# SCH_ESP32-WROOM_2022-01-13.net
KiCad netlist of a schematic drawn in EasyEDA
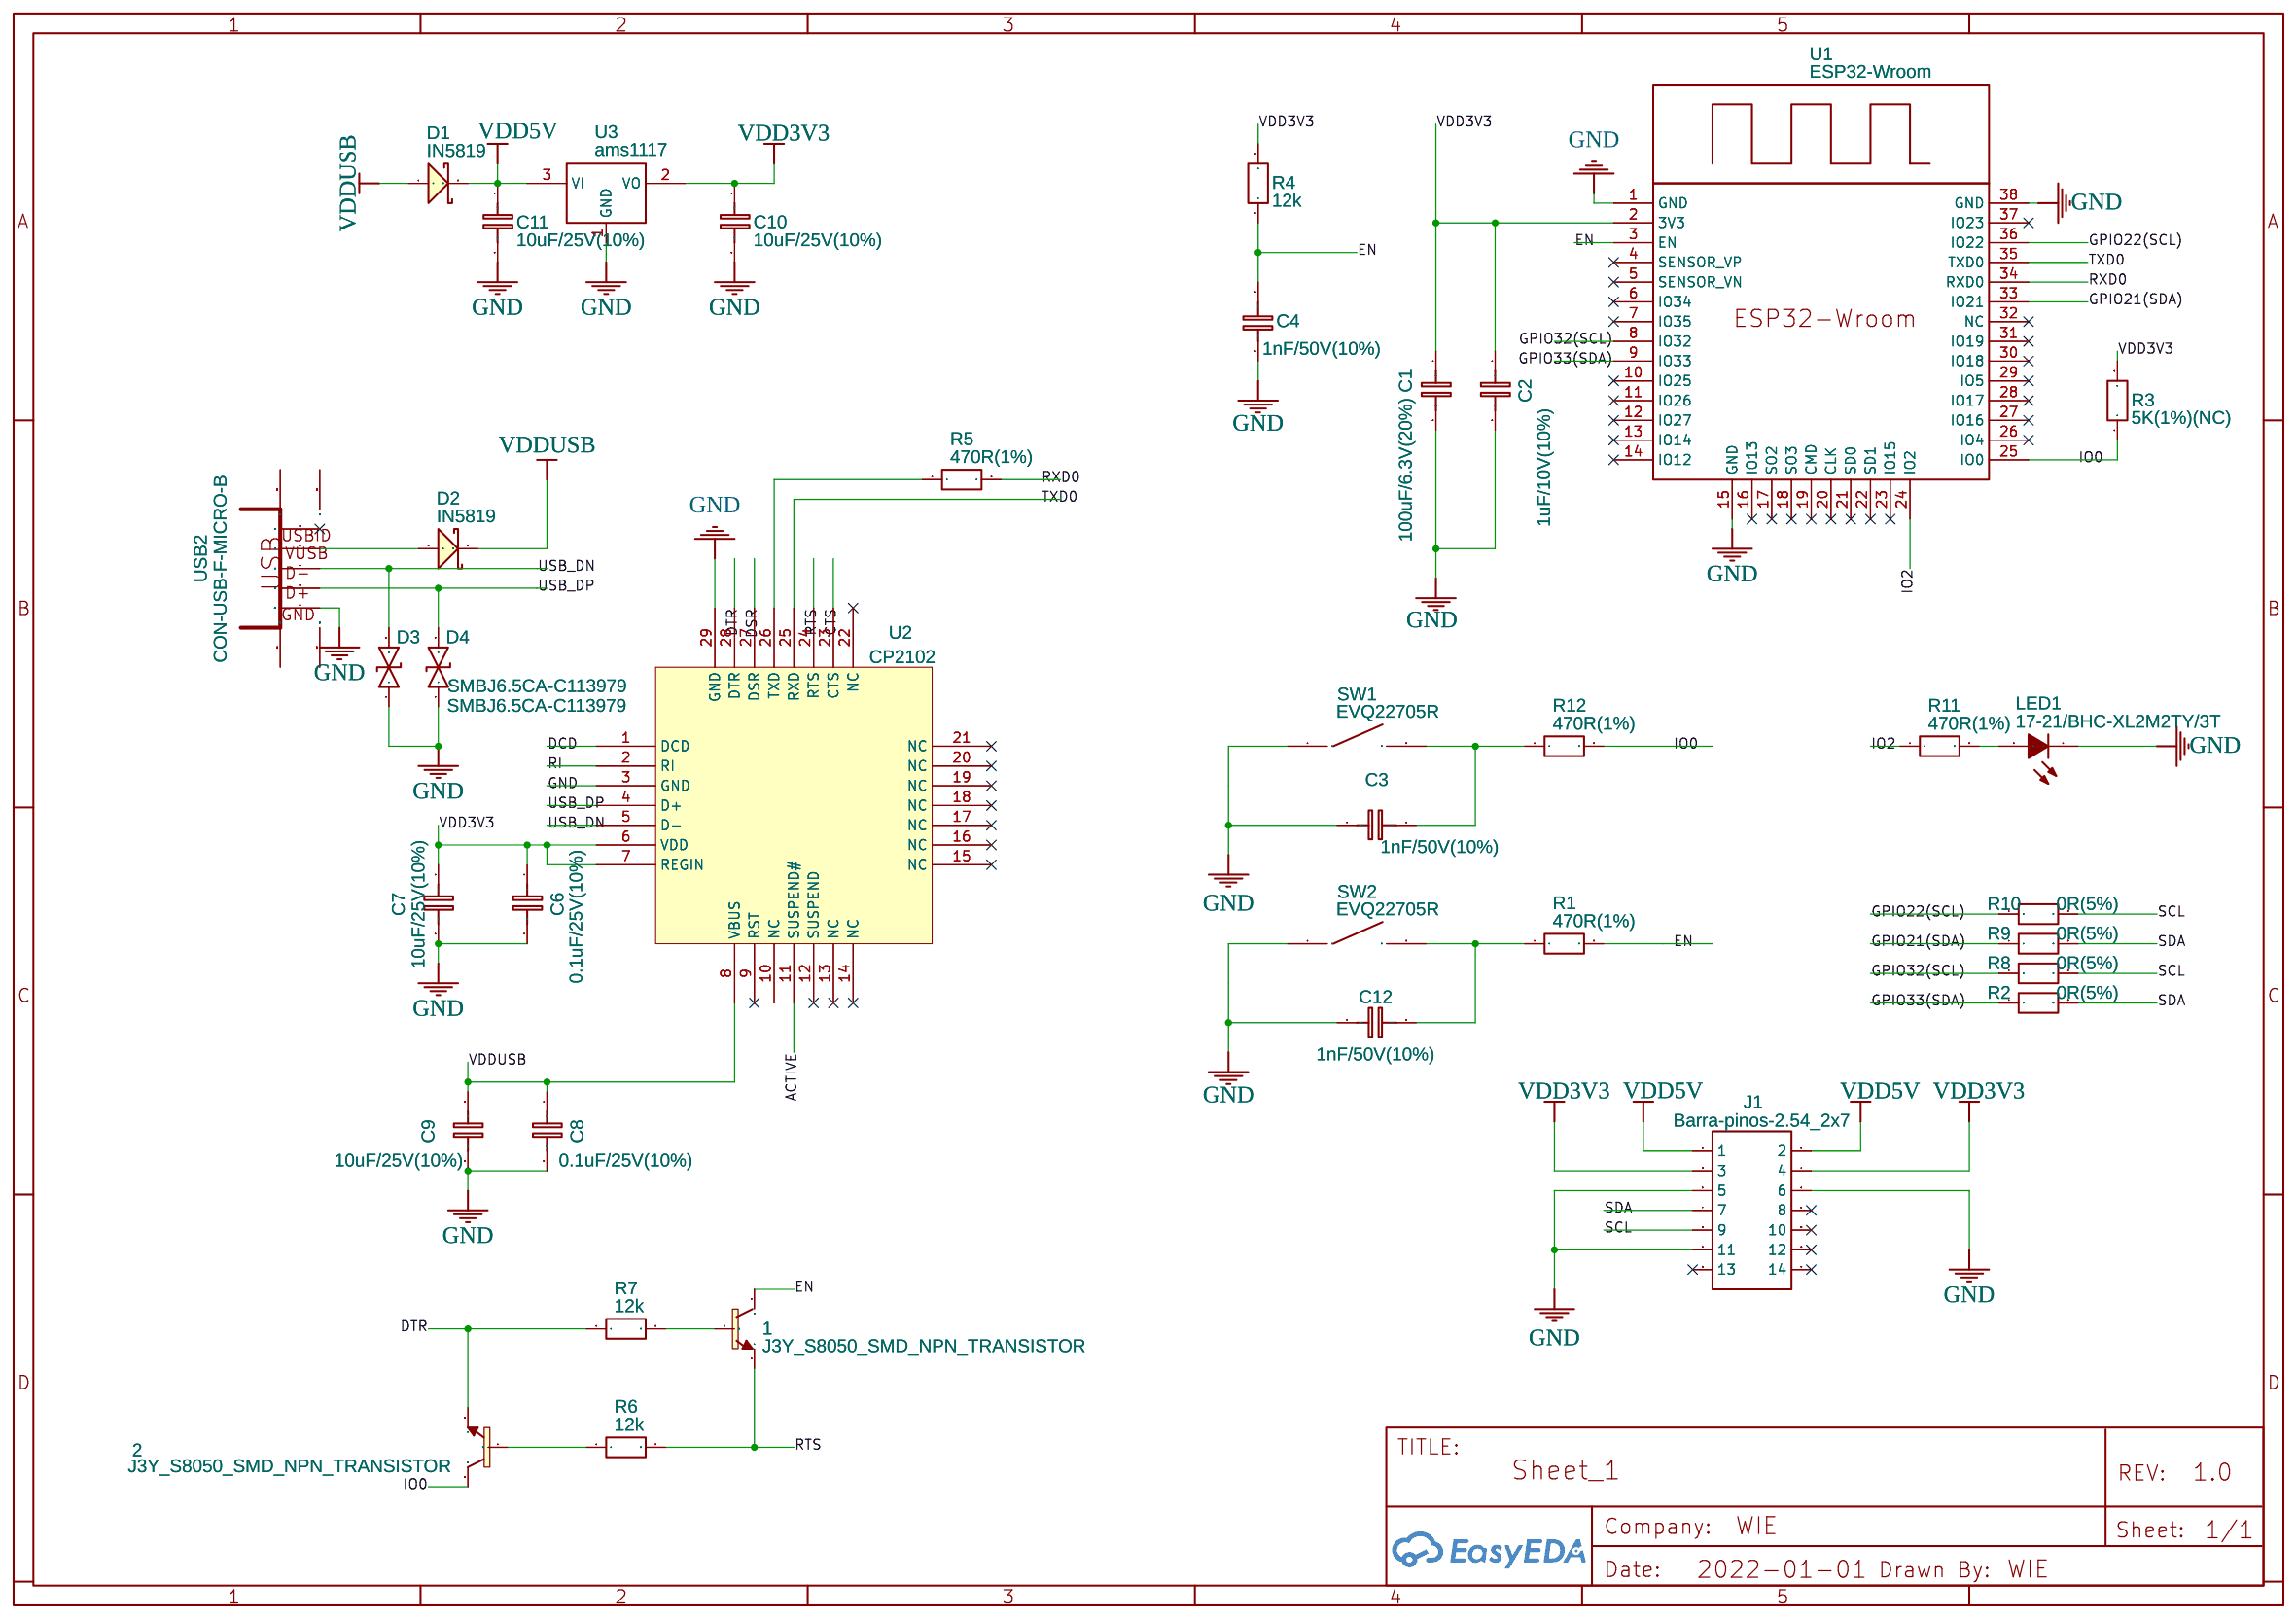
[diagram p0: schematic sheet]

(export (version "E")
  (design (tool "Eeschema 10.0.6"))
  (components
    (comp (ref "1")
      (value "J3Y_S8050_SMD_NPN_TRANSISTOR")
      (libsource (lib "") (part "J3Y_S8050_SMD_NPN_TRANSISTOR_1"))
    )
    (comp (ref "2")
      (value "J3Y_S8050_SMD_NPN_TRANSISTOR")
      (libsource (lib "") (part "J3Y_S8050_SMD_NPN_TRANSISTOR"))
    )
    (comp (ref "C1") (value "100uF/6.3V(20%)") (libsource (lib "") (part "Cap_0805_EU_1")))
    (comp (ref "C2") (value "1uF/10V(10%)") (libsource (lib "") (part "Cap_0805_EU_1")))
    (comp (ref "C3") (value "1nF/50V(10%)") (libsource (lib "") (part "Cap_0805_EU")))
    (comp (ref "C4") (value "1nF/50V(10%)") (libsource (lib "") (part "Cap_0805_EU_4")))
    (comp (ref "C6") (value "0.1uF/25V(10%)") (libsource (lib "") (part "Cap_0805_EU_2")))
    (comp (ref "C7") (value "10uF/25V(10%)") (libsource (lib "") (part "Cap_0805_EU_2")))
    (comp (ref "C8") (value "0.1uF/25V(10%)") (libsource (lib "") (part "Cap_0805_EU_2")))
    (comp (ref "C9") (value "10uF/25V(10%)") (libsource (lib "") (part "Cap_0805_EU_2")))
    (comp (ref "C10") (value "10uF/25V(10%)") (libsource (lib "") (part "Cap_0805_EU_3")))
    (comp (ref "C11") (value "10uF/25V(10%)") (libsource (lib "") (part "Cap_0805_EU_3")))
    (comp (ref "C12") (value "1nF/50V(10%)") (libsource (lib "") (part "Cap_0805_EU")))
    (comp (ref "D1") (value "IN5819") (libsource (lib "") (part "IN5819")))
    (comp (ref "D2") (value "IN5819") (libsource (lib "") (part "IN5819")))
    (comp (ref "D3")
      (value "SMBJ6.5CA-C113979")
      (fields (field (name "BOM_Manufacturer Part") "SMBJ6.5CA") (field (name "BOM_Supplier Part") "C113979"))
      (libsource (lib "") (part "SMBJ6.5CA-C113979"))
    )
    (comp (ref "D4")
      (value "SMBJ6.5CA-C113979")
      (fields (field (name "BOM_Manufacturer Part") "SMBJ6.5CA") (field (name "BOM_Supplier Part") "C113979"))
      (libsource (lib "") (part "SMBJ6.5CA-C113979"))
    )
    (comp (ref "J1")
      (value "Barra-pinos-2.54_2x7")
      (fields
        (field (name "BOM_Manufacturer Part") "Double row of needle2X7P 2.54mm")
        (field (name "BOM_Supplier Part") "C71397")
      )
      (libsource (lib "") (part "Barra-pinos-2.54_2x7"))
    )
    (comp (ref "LED1")
      (value "17-21/BHC-XL2M2TY/3T")
      (fields (field (name "BOM_Supplier Part") "C72035"))
      (libsource (lib "") (part "17-21/BHC-XL2M2TY/3T"))
    )
    (comp (ref "R1") (value "470R(1%)") (libsource (lib "") (part "Res_0805(1/8W)_EU")))
    (comp (ref "R2") (value "0R(5%)") (libsource (lib "") (part "Res_0805(1/8W)_EU")))
    (comp (ref "R3") (value "5K(1%)(NC)") (libsource (lib "") (part "Res_0805(1/8W)_EU_1")))
    (comp (ref "R4") (value "12k") (libsource (lib "") (part "Res_0805(1/8W)_EU_1")))
    (comp (ref "R5") (value "470R(1%)") (libsource (lib "") (part "Res_0805(1/8W)_EU")))
    (comp (ref "R6") (value "12k") (libsource (lib "") (part "Res_0805(1/8W)_EU")))
    (comp (ref "R7") (value "12k") (libsource (lib "") (part "Res_0805(1/8W)_EU")))
    (comp (ref "R8") (value "0R(5%)") (libsource (lib "") (part "Res_0805(1/8W)_EU")))
    (comp (ref "R9") (value "0R(5%)") (libsource (lib "") (part "Res_0805(1/8W)_EU")))
    (comp (ref "R10") (value "0R(5%)") (libsource (lib "") (part "Res_0805(1/8W)_EU")))
    (comp (ref "R11") (value "470R(1%)") (libsource (lib "") (part "Res_0805(1/8W)_EU")))
    (comp (ref "R12") (value "470R(1%)") (libsource (lib "") (part "Res_0805(1/8W)_EU")))
    (comp (ref "SW1")
      (value "EVQ22705R")
      (fields (field (name "BOM_Supplier Part") "C79156"))
      (libsource (lib "") (part "Unknown_680_-435"))
    )
    (comp (ref "SW2")
      (value "EVQ22705R")
      (fields (field (name "BOM_Supplier Part") "C79156"))
      (libsource (lib "") (part "Unknown_680_-335"))
    )
    (comp (ref "U1") (value "ESP32-Wroom") (libsource (lib "") (part "ESP32-Wroom")))
    (comp (ref "U2") (value "CP2102") (libsource (lib "") (part "CP2102")))
    (comp (ref "U3") (value "ams1117") (libsource (lib "") (part "ams1117")))
    (comp (ref "USB2") (value "CON-USB-F-MICRO-B") (libsource (lib "") (part "CON-USB-F-MICRO-B")))
  )
  (nets
    (net (code "1") (name "/ACTIVE") (class "Default")
      (node (ref "U2") (pin "11") (pinfunction "SUSPEND#_11") (pintype "unspecified"))
    )
    (net (code "2") (name "/CTS") (class "Default")
      (node (ref "U2") (pin "23") (pinfunction "CTS_23") (pintype "unspecified"))
    )
    (net (code "3") (name "/DCD") (class "Default")
      (node (ref "U2") (pin "1") (pinfunction "DCD_1") (pintype "unspecified"))
    )
    (net (code "4") (name "/DSR") (class "Default")
      (node (ref "U2") (pin "27") (pinfunction "DSR_27") (pintype "unspecified"))
    )
    (net (code "5") (name "/DTR") (class "Default")
      (node (ref "2") (pin "3") (pinfunction "E_3") (pintype "bidirectional"))
      (node (ref "R7") (pin "1") (pinfunction "1_1") (pintype "unspecified"))
      (node (ref "U2") (pin "28") (pinfunction "DTR_28") (pintype "unspecified"))
    )
    (net (code "6") (name "/EN") (class "Default")
      (node (ref "1") (pin "2") (pinfunction "C_2") (pintype "bidirectional"))
      (node (ref "C4") (pin "2") (pinfunction "2_2") (pintype "unspecified"))
      (node (ref "R1") (pin "2") (pinfunction "2_2") (pintype "unspecified"))
      (node (ref "R4") (pin "1") (pinfunction "1_1") (pintype "unspecified"))
      (node (ref "U1") (pin "3") (pinfunction "EN_3") (pintype "unspecified"))
    )
    (net (code "7") (name "/GPIO21(SDA)") (class "Default")
      (node (ref "R9") (pin "1") (pinfunction "1_1") (pintype "unspecified"))
      (node (ref "U1") (pin "33") (pinfunction "IO21_33") (pintype "unspecified"))
    )
    (net (code "8") (name "/GPIO22(SCL)") (class "Default")
      (node (ref "R10") (pin "1") (pinfunction "1_1") (pintype "unspecified"))
      (node (ref "U1") (pin "36") (pinfunction "IO22_36") (pintype "unspecified"))
    )
    (net (code "9") (name "/GPIO32(SCL)") (class "Default")
      (node (ref "R8") (pin "1") (pinfunction "1_1") (pintype "unspecified"))
      (node (ref "U1") (pin "8") (pinfunction "IO32_8") (pintype "unspecified"))
    )
    (net (code "10") (name "/GPIO33(SDA)") (class "Default")
      (node (ref "R2") (pin "1") (pinfunction "1_1") (pintype "unspecified"))
      (node (ref "U1") (pin "9") (pinfunction "IO33_9") (pintype "unspecified"))
    )
    (net (code "11") (name "/IO0") (class "Default")
      (node (ref "2") (pin "2") (pinfunction "C_2") (pintype "bidirectional"))
      (node (ref "R12") (pin "2") (pinfunction "2_2") (pintype "unspecified"))
      (node (ref "R3") (pin "1") (pinfunction "1_1") (pintype "unspecified"))
      (node (ref "U1") (pin "25") (pinfunction "IO0_25") (pintype "unspecified"))
    )
    (net (code "12") (name "/IO2") (class "Default")
      (node (ref "R11") (pin "1") (pinfunction "1_1") (pintype "unspecified"))
      (node (ref "U1") (pin "24") (pinfunction "IO2_24") (pintype "unspecified"))
    )
    (net (code "13") (name "/RI") (class "Default")
      (node (ref "U2") (pin "2") (pinfunction "RI_2") (pintype "unspecified"))
    )
    (net (code "14") (name "/RTS") (class "Default")
      (node (ref "1") (pin "3") (pinfunction "E_3") (pintype "bidirectional"))
      (node (ref "R6") (pin "2") (pinfunction "2_2") (pintype "unspecified"))
      (node (ref "U2") (pin "24") (pinfunction "RTS_24") (pintype "unspecified"))
    )
    (net (code "15") (name "/RXD0") (class "Default")
      (node (ref "R5") (pin "2") (pinfunction "2_2") (pintype "unspecified"))
      (node (ref "U1") (pin "34") (pinfunction "RXD0_34") (pintype "unspecified"))
    )
    (net (code "16") (name "/SCL") (class "Default")
      (node (ref "J1") (pin "9") (pinfunction "9_9") (pintype "input"))
      (node (ref "R10") (pin "2") (pinfunction "2_2") (pintype "unspecified"))
      (node (ref "R8") (pin "2") (pinfunction "2_2") (pintype "unspecified"))
    )
    (net (code "17") (name "/SDA") (class "Default")
      (node (ref "J1") (pin "7") (pinfunction "7_7") (pintype "input"))
      (node (ref "R2") (pin "2") (pinfunction "2_2") (pintype "unspecified"))
      (node (ref "R9") (pin "2") (pinfunction "2_2") (pintype "unspecified"))
    )
    (net (code "18") (name "/TXD0") (class "Default")
      (node (ref "U1") (pin "35") (pinfunction "TXD0_35") (pintype "unspecified"))
      (node (ref "U2") (pin "25") (pinfunction "RXD_25") (pintype "unspecified"))
    )
    (net (code "19") (name "/USB_DN") (class "Default")
      (node (ref "D3") (pin "2") (pinfunction "2_2") (pintype "unspecified"))
      (node (ref "U2") (pin "5") (pinfunction "D-_5") (pintype "unspecified"))
      (node (ref "USB2") (pin "P2") (pinfunction "D-_P2") (pintype "unspecified"))
    )
    (net (code "20") (name "/USB_DP") (class "Default")
      (node (ref "D4") (pin "2") (pinfunction "2_2") (pintype "unspecified"))
      (node (ref "U2") (pin "4") (pinfunction "D+_4") (pintype "unspecified"))
      (node (ref "USB2") (pin "P3") (pinfunction "D+_P3") (pintype "unspecified"))
    )
    (net (code "21") (name "GND") (class "Default")
      (node (ref "C1") (pin "2") (pinfunction "2_2") (pintype "unspecified"))
      (node (ref "C10") (pin "2") (pinfunction "2_2") (pintype "unspecified"))
      (node (ref "C11") (pin "2") (pinfunction "2_2") (pintype "unspecified"))
      (node (ref "C12") (pin "1") (pinfunction "1_1") (pintype "unspecified"))
      (node (ref "C2") (pin "2") (pinfunction "2_2") (pintype "unspecified"))
      (node (ref "C3") (pin "1") (pinfunction "1_1") (pintype "unspecified"))
      (node (ref "C4") (pin "1") (pinfunction "1_1") (pintype "unspecified"))
      (node (ref "C6") (pin "2") (pinfunction "2_2") (pintype "unspecified"))
      (node (ref "C7") (pin "2") (pinfunction "2_2") (pintype "unspecified"))
      (node (ref "C8") (pin "2") (pinfunction "2_2") (pintype "unspecified"))
      (node (ref "C9") (pin "2") (pinfunction "2_2") (pintype "unspecified"))
      (node (ref "D3") (pin "1") (pinfunction "1_1") (pintype "unspecified"))
      (node (ref "D4") (pin "1") (pinfunction "1_1") (pintype "unspecified"))
      (node (ref "J1") (pin "11") (pinfunction "11_11") (pintype "input"))
      (node (ref "J1") (pin "5") (pinfunction "5_5") (pintype "input"))
      (node (ref "J1") (pin "6") (pinfunction "6_6") (pintype "input"))
      (node (ref "LED1") (pin "1") (pinfunction "-_1") (pintype "input"))
      (node (ref "SW1") (pin "1") (pinfunction "1_1") (pintype "input"))
      (node (ref "SW2") (pin "1") (pinfunction "1_1") (pintype "input"))
      (node (ref "U1") (pin "1") (pinfunction "GND_1") (pintype "unspecified"))
      (node (ref "U1") (pin "15") (pinfunction "GND_15") (pintype "unspecified"))
      (node (ref "U1") (pin "38") (pinfunction "GND_38") (pintype "unspecified"))
      (node (ref "U2") (pin "29") (pinfunction "GND_29") (pintype "unspecified"))
      (node (ref "U2") (pin "3") (pinfunction "GND_3") (pintype "unspecified"))
      (node (ref "U3") (pin "1") (pinfunction "GND_1") (pintype "input"))
      (node (ref "USB2") (pin "P4") (pinfunction "USBID_P4") (pintype "unspecified"))
    )
    (net (code "22") (name "Net-(1-B)") (class "Default")
      (node (ref "1") (pin "1") (pinfunction "B_1") (pintype "bidirectional"))
      (node (ref "R7") (pin "2") (pinfunction "2_2") (pintype "unspecified"))
    )
    (net (code "23") (name "Net-(2-B)") (class "Default")
      (node (ref "2") (pin "1") (pinfunction "B_1") (pintype "bidirectional"))
      (node (ref "R6") (pin "1") (pinfunction "1_1") (pintype "unspecified"))
    )
    (net (code "24") (name "Net-(C3-Pad2)") (class "Default")
      (node (ref "C3") (pin "2") (pinfunction "2_2") (pintype "unspecified"))
      (node (ref "R12") (pin "1") (pinfunction "1_1") (pintype "unspecified"))
      (node (ref "SW1") (pin "2") (pinfunction "2_2") (pintype "input"))
    )
    (net (code "25") (name "Net-(C12-Pad2)") (class "Default")
      (node (ref "C12") (pin "2") (pinfunction "2_2") (pintype "unspecified"))
      (node (ref "R1") (pin "1") (pinfunction "1_1") (pintype "unspecified"))
      (node (ref "SW2") (pin "2") (pinfunction "2_2") (pintype "input"))
    )
    (net (code "26") (name "Net-(LED1-+)") (class "Default")
      (node (ref "LED1") (pin "2") (pinfunction "+_2") (pintype "input"))
      (node (ref "R11") (pin "2") (pinfunction "2_2") (pintype "unspecified"))
    )
    (net (code "27") (name "Net-(U2-TXD)") (class "Default")
      (node (ref "R5") (pin "1") (pinfunction "1_1") (pintype "unspecified"))
      (node (ref "U2") (pin "26") (pinfunction "TXD_26") (pintype "unspecified"))
    )
    (net (code "28") (name "Net-(USB2-VUSB)") (class "Default")
      (node (ref "D2") (pin "1") (pinfunction "1_1") (pintype "unspecified"))
      (node (ref "USB2") (pin "P1") (pinfunction "VUSB_P1") (pintype "unspecified"))
    )
    (net (code "29") (name "VDD3V3") (class "Default")
      (node (ref "C1") (pin "1") (pinfunction "1_1") (pintype "unspecified"))
      (node (ref "C10") (pin "1") (pinfunction "1_1") (pintype "unspecified"))
      (node (ref "C2") (pin "1") (pinfunction "1_1") (pintype "unspecified"))
      (node (ref "C6") (pin "1") (pinfunction "1_1") (pintype "unspecified"))
      (node (ref "C7") (pin "1") (pinfunction "1_1") (pintype "unspecified"))
      (node (ref "J1") (pin "3") (pinfunction "3_3") (pintype "input"))
      (node (ref "J1") (pin "4") (pinfunction "4_4") (pintype "input"))
      (node (ref "R3") (pin "2") (pinfunction "2_2") (pintype "unspecified"))
      (node (ref "R4") (pin "2") (pinfunction "2_2") (pintype "unspecified"))
      (node (ref "U1") (pin "2") (pinfunction "3V3_2") (pintype "unspecified"))
      (node (ref "U2") (pin "6") (pinfunction "VDD_6") (pintype "unspecified"))
      (node (ref "U2") (pin "7") (pinfunction "REGIN_7") (pintype "unspecified"))
      (node (ref "U3") (pin "2") (pinfunction "VO_2") (pintype "unspecified"))
    )
    (net (code "30") (name "VDD5V") (class "Default")
      (node (ref "C11") (pin "1") (pinfunction "1_1") (pintype "unspecified"))
      (node (ref "D1") (pin "2") (pinfunction "2_2") (pintype "unspecified"))
      (node (ref "J1") (pin "1") (pinfunction "1_1") (pintype "input"))
      (node (ref "J1") (pin "2") (pinfunction "2_2") (pintype "input"))
      (node (ref "U3") (pin "3") (pinfunction "VI_3") (pintype "input"))
    )
    (net (code "31") (name "VDDUSB") (class "Default")
      (node (ref "C8") (pin "1") (pinfunction "1_1") (pintype "unspecified"))
      (node (ref "C9") (pin "1") (pinfunction "1_1") (pintype "unspecified"))
      (node (ref "D1") (pin "1") (pinfunction "1_1") (pintype "unspecified"))
      (node (ref "D2") (pin "2") (pinfunction "2_2") (pintype "unspecified"))
      (node (ref "U2") (pin "8") (pinfunction "VBUS_8") (pintype "unspecified"))
    )
    (net (code "32") (name "unconnected-(J1-Pad8)") (class "Default")
      (node (ref "J1") (pin "8") (pinfunction "8_8") (pintype "input+no_connect"))
    )
    (net (code "33") (name "unconnected-(J1-Pad10)") (class "Default")
      (node (ref "J1") (pin "10") (pinfunction "10_10") (pintype "input+no_connect"))
    )
    (net (code "34") (name "unconnected-(J1-Pad12)") (class "Default")
      (node (ref "J1") (pin "12") (pinfunction "12_12") (pintype "input+no_connect"))
    )
    (net (code "35") (name "unconnected-(J1-Pad13)") (class "Default")
      (node (ref "J1") (pin "13") (pinfunction "13_13") (pintype "input+no_connect"))
    )
    (net (code "36") (name "unconnected-(J1-Pad14)") (class "Default")
      (node (ref "J1") (pin "14") (pinfunction "14_14") (pintype "input+no_connect"))
    )
    (net (code "37") (name "unconnected-(U1-CLK-Pad20)") (class "Default")
      (node (ref "U1") (pin "20") (pinfunction "CLK_20") (pintype "unspecified+no_connect"))
    )
    (net (code "38") (name "unconnected-(U1-CMD-Pad19)") (class "Default")
      (node (ref "U1") (pin "19") (pinfunction "CMD_19") (pintype "unspecified+no_connect"))
    )
    (net (code "39") (name "unconnected-(U1-IO4-Pad26)") (class "Default")
      (node (ref "U1") (pin "26") (pinfunction "IO4_26") (pintype "unspecified+no_connect"))
    )
    (net (code "40") (name "unconnected-(U1-IO5-Pad29)") (class "Default")
      (node (ref "U1") (pin "29") (pinfunction "IO5_29") (pintype "unspecified+no_connect"))
    )
    (net (code "41") (name "unconnected-(U1-IO12-Pad14)") (class "Default")
      (node (ref "U1") (pin "14") (pinfunction "IO12_14") (pintype "unspecified+no_connect"))
    )
    (net (code "42") (name "unconnected-(U1-IO13-Pad16)") (class "Default")
      (node (ref "U1") (pin "16") (pinfunction "IO13_16") (pintype "unspecified+no_connect"))
    )
    (net (code "43") (name "unconnected-(U1-IO14-Pad13)") (class "Default")
      (node (ref "U1") (pin "13") (pinfunction "IO14_13") (pintype "unspecified+no_connect"))
    )
    (net (code "44") (name "unconnected-(U1-IO15-Pad23)") (class "Default")
      (node (ref "U1") (pin "23") (pinfunction "IO15_23") (pintype "unspecified+no_connect"))
    )
    (net (code "45") (name "unconnected-(U1-IO16-Pad27)") (class "Default")
      (node (ref "U1") (pin "27") (pinfunction "IO16_27") (pintype "unspecified+no_connect"))
    )
    (net (code "46") (name "unconnected-(U1-IO17-Pad28)") (class "Default")
      (node (ref "U1") (pin "28") (pinfunction "IO17_28") (pintype "unspecified+no_connect"))
    )
    (net (code "47") (name "unconnected-(U1-IO18-Pad30)") (class "Default")
      (node (ref "U1") (pin "30") (pinfunction "IO18_30") (pintype "unspecified+no_connect"))
    )
    (net (code "48") (name "unconnected-(U1-IO19-Pad31)") (class "Default")
      (node (ref "U1") (pin "31") (pinfunction "IO19_31") (pintype "unspecified+no_connect"))
    )
    (net (code "49") (name "unconnected-(U1-IO23-Pad37)") (class "Default")
      (node (ref "U1") (pin "37") (pinfunction "IO23_37") (pintype "unspecified+no_connect"))
    )
    (net (code "50") (name "unconnected-(U1-IO25-Pad10)") (class "Default")
      (node (ref "U1") (pin "10") (pinfunction "IO25_10") (pintype "unspecified+no_connect"))
    )
    (net (code "51") (name "unconnected-(U1-IO26-Pad11)") (class "Default")
      (node (ref "U1") (pin "11") (pinfunction "IO26_11") (pintype "unspecified+no_connect"))
    )
    (net (code "52") (name "unconnected-(U1-IO27-Pad12)") (class "Default")
      (node (ref "U1") (pin "12") (pinfunction "IO27_12") (pintype "unspecified+no_connect"))
    )
    (net (code "53") (name "unconnected-(U1-IO34-Pad6)") (class "Default")
      (node (ref "U1") (pin "6") (pinfunction "IO34_6") (pintype "unspecified+no_connect"))
    )
    (net (code "54") (name "unconnected-(U1-IO35-Pad7)") (class "Default")
      (node (ref "U1") (pin "7") (pinfunction "IO35_7") (pintype "unspecified+no_connect"))
    )
    (net (code "55") (name "unconnected-(U1-NC-Pad32)") (class "Default")
      (node (ref "U1") (pin "32") (pinfunction "NC_32") (pintype "unspecified+no_connect"))
    )
    (net (code "56") (name "unconnected-(U1-SD0-Pad21)") (class "Default")
      (node (ref "U1") (pin "21") (pinfunction "SD0_21") (pintype "unspecified+no_connect"))
    )
    (net (code "57") (name "unconnected-(U1-SD1-Pad22)") (class "Default")
      (node (ref "U1") (pin "22") (pinfunction "SD1_22") (pintype "unspecified+no_connect"))
    )
    (net (code "58") (name "unconnected-(U1-SENSOR_VN-Pad5)") (class "Default")
      (node (ref "U1") (pin "5") (pinfunction "SENSOR_VN_5") (pintype "unspecified+no_connect"))
    )
    (net (code "59") (name "unconnected-(U1-SENSOR_VP-Pad4)") (class "Default")
      (node (ref "U1") (pin "4") (pinfunction "SENSOR_VP_4") (pintype "unspecified+no_connect"))
    )
    (net (code "60") (name "unconnected-(U1-SO2-Pad17)") (class "Default")
      (node (ref "U1") (pin "17") (pinfunction "SO2_17") (pintype "unspecified+no_connect"))
    )
    (net (code "61") (name "unconnected-(U1-SO3-Pad18)") (class "Default")
      (node (ref "U1") (pin "18") (pinfunction "SO3_18") (pintype "unspecified+no_connect"))
    )
    (net (code "62") (name "unconnected-(U2-NC-Pad10)") (class "Default")
      (node (ref "U2") (pin "10") (pinfunction "NC_10") (pintype "unspecified"))
    )
    (net (code "63") (name "unconnected-(U2-NC-Pad13)") (class "Default")
      (node (ref "U2") (pin "13") (pinfunction "NC_13") (pintype "unspecified+no_connect"))
    )
    (net (code "64") (name "unconnected-(U2-NC-Pad14)") (class "Default")
      (node (ref "U2") (pin "14") (pinfunction "NC_14") (pintype "unspecified+no_connect"))
    )
    (net (code "65") (name "unconnected-(U2-NC-Pad15)") (class "Default")
      (node (ref "U2") (pin "15") (pinfunction "NC_15") (pintype "unspecified+no_connect"))
    )
    (net (code "66") (name "unconnected-(U2-NC-Pad16)") (class "Default")
      (node (ref "U2") (pin "16") (pinfunction "NC_16") (pintype "unspecified+no_connect"))
    )
    (net (code "67") (name "unconnected-(U2-NC-Pad17)") (class "Default")
      (node (ref "U2") (pin "17") (pinfunction "NC_17") (pintype "unspecified+no_connect"))
    )
    (net (code "68") (name "unconnected-(U2-NC-Pad18)") (class "Default")
      (node (ref "U2") (pin "18") (pinfunction "NC_18") (pintype "unspecified+no_connect"))
    )
    (net (code "69") (name "unconnected-(U2-NC-Pad19)") (class "Default")
      (node (ref "U2") (pin "19") (pinfunction "NC_19") (pintype "unspecified+no_connect"))
    )
    (net (code "70") (name "unconnected-(U2-NC-Pad20)") (class "Default")
      (node (ref "U2") (pin "20") (pinfunction "NC_20") (pintype "unspecified+no_connect"))
    )
    (net (code "71") (name "unconnected-(U2-NC-Pad21)") (class "Default")
      (node (ref "U2") (pin "21") (pinfunction "NC_21") (pintype "unspecified+no_connect"))
    )
    (net (code "72") (name "unconnected-(U2-NC-Pad22)") (class "Default")
      (node (ref "U2") (pin "22") (pinfunction "NC_22") (pintype "unspecified+no_connect"))
    )
    (net (code "73") (name "unconnected-(U2-RST-Pad9)") (class "Default")
      (node (ref "U2") (pin "9") (pinfunction "RST_9") (pintype "unspecified+no_connect"))
    )
    (net (code "74") (name "unconnected-(U2-SUSPEND-Pad12)") (class "Default")
      (node (ref "U2") (pin "12") (pinfunction "SUSPEND_12") (pintype "unspecified+no_connect"))
    )
    (net (code "75") (name "unconnected-(USB2-BODY-PadBODY@1)") (class "Default")
      (node (ref "USB2") (pin "BODY@1") (pinfunction "BODY_BODY@1") (pintype "unspecified"))
    )
    (net (code "76") (name "unconnected-(USB2-BODY-PadBODY@2)") (class "Default")
      (node (ref "USB2") (pin "BODY@2") (pinfunction "BODY_BODY@2") (pintype "unspecified"))
    )
    (net (code "77") (name "unconnected-(USB2-BODY-PadBODY@3)") (class "Default")
      (node (ref "USB2") (pin "BODY@3") (pinfunction "BODY_BODY@3") (pintype "unspecified"))
    )
    (net (code "78") (name "unconnected-(USB2-BODY-PadBODY@4)") (class "Default")
      (node (ref "USB2") (pin "BODY@4") (pinfunction "BODY_BODY@4") (pintype "unspecified"))
    )
    (net (code "79") (name "unconnected-(USB2-GND-PadP5)") (class "Default")
      (node (ref "USB2") (pin "P5") (pinfunction "GND_P5") (pintype "unspecified+no_connect"))
    )
  )
)
